# f394.net
KiCad netlist of a schematic drawn in EAGLE
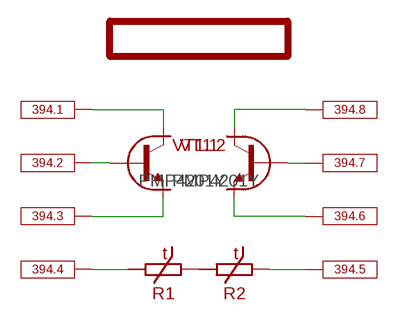
[diagram p0: schematic, sheet 1]

(export (version "E")
  (design (tool "Eeschema 10.0.6"))
  (components
    (comp (ref "394")
      (value "DIP8")
      (footprint "eagle-import:BA3760X8")
      (libsource (lib "eagle-import") (part "DIP8"))
    )
    (comp (ref "R1")
      (value "ERA-V33J102V")
      (footprint "eagle-import:R-0603")
      (libsource (lib "eagle-import") (part "ERA-?33JVV102"))
    )
    (comp (ref "R2")
      (value "ERA-V33J102V")
      (footprint "eagle-import:R-0603")
      (libsource (lib "eagle-import") (part "ERA-?33JVV102"))
    )
    (comp (ref "VT1")
      (value "PMP4201Y")
      (footprint "eagle-import:SOT363_PHILIPS")
      (libsource (lib "eagle-import") (part "PMP4201Y"))
    )
  )
  (nets
    (net (code "1") (name "Net-(R1-A)") (class "Default")
      (node (ref "394") (pin "B4") (pinfunction "PIN_B4") (pintype "bidirectional"))
      (node (ref "394") (pin "T4") (pinfunction "PIN_T4") (pintype "bidirectional"))
      (node (ref "R1") (pin "1") (pinfunction "A_1") (pintype "passive"))
    )
    (net (code "2") (name "Net-(R1-E)") (class "Default")
      (node (ref "R1") (pin "2") (pinfunction "E_2") (pintype "passive"))
      (node (ref "R2") (pin "1") (pinfunction "A_1") (pintype "passive"))
    )
    (net (code "3") (name "Net-(R2-E)") (class "Default")
      (node (ref "394") (pin "B5") (pinfunction "PIN_B5") (pintype "bidirectional"))
      (node (ref "394") (pin "T5") (pinfunction "PIN_T5") (pintype "bidirectional"))
      (node (ref "R2") (pin "2") (pinfunction "E_2") (pintype "passive"))
    )
    (net (code "4") (name "Net-(VT1A-B)") (class "Default")
      (node (ref "394") (pin "B2") (pinfunction "PIN_B2") (pintype "bidirectional"))
      (node (ref "394") (pin "T2") (pinfunction "PIN_T2") (pintype "bidirectional"))
      (node (ref "VT1") (pin "1") (pinfunction "B_1") (pintype "passive"))
    )
    (net (code "5") (name "Net-(VT1A-C)") (class "Default")
      (node (ref "394") (pin "B1") (pinfunction "PIN_B1") (pintype "bidirectional"))
      (node (ref "394") (pin "T1") (pinfunction "PIN_T1") (pintype "bidirectional"))
      (node (ref "VT1") (pin "6") (pinfunction "C_6") (pintype "passive"))
    )
    (net (code "6") (name "Net-(VT1A-E)") (class "Default")
      (node (ref "394") (pin "B3") (pinfunction "PIN_B3") (pintype "bidirectional"))
      (node (ref "394") (pin "T3") (pinfunction "PIN_T3") (pintype "bidirectional"))
      (node (ref "VT1") (pin "5") (pinfunction "E_5") (pintype "passive"))
    )
    (net (code "7") (name "Net-(VT1B-B)") (class "Default")
      (node (ref "394") (pin "B7") (pinfunction "PIN_B7") (pintype "bidirectional"))
      (node (ref "394") (pin "T7") (pinfunction "PIN_T7") (pintype "bidirectional"))
      (node (ref "VT1") (pin "2") (pinfunction "B_2") (pintype "passive"))
    )
    (net (code "8") (name "Net-(VT1B-C)") (class "Default")
      (node (ref "394") (pin "B8") (pinfunction "PIN_B8") (pintype "bidirectional"))
      (node (ref "394") (pin "T8") (pinfunction "PIN_T8") (pintype "bidirectional"))
      (node (ref "VT1") (pin "3") (pinfunction "C_3") (pintype "passive"))
    )
    (net (code "9") (name "Net-(VT1B-E)") (class "Default")
      (node (ref "394") (pin "B6") (pinfunction "PIN_B6") (pintype "bidirectional"))
      (node (ref "394") (pin "T6") (pinfunction "PIN_T6") (pintype "bidirectional"))
      (node (ref "VT1") (pin "4") (pinfunction "E_4") (pintype "passive"))
    )
  )
)
